# Micro.net
KiCad netlist of a schematic drawn in Altium Designer
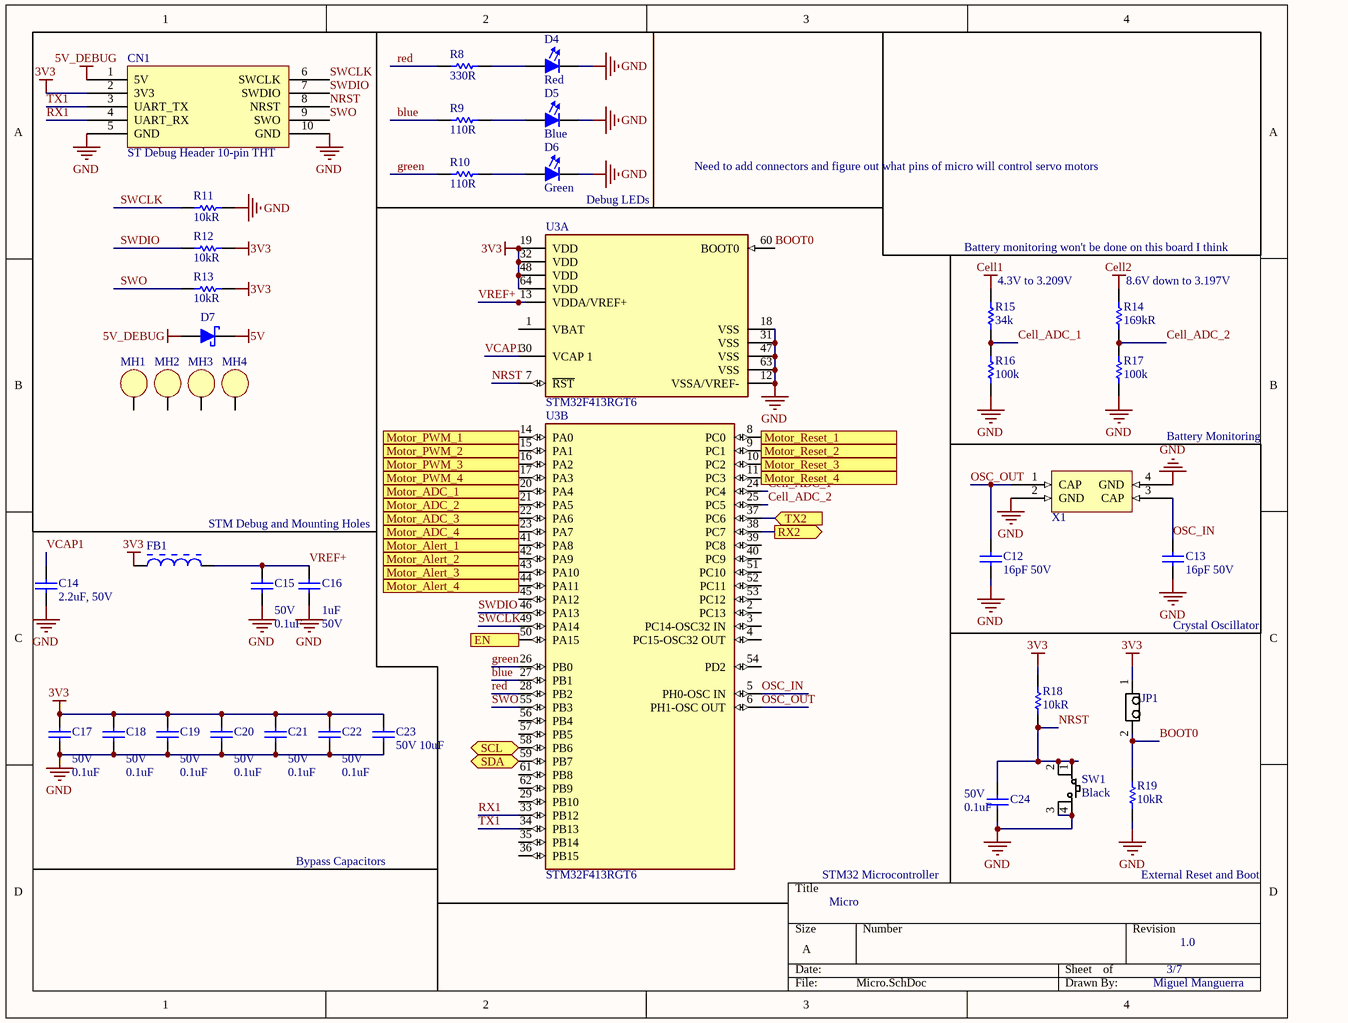
[diagram p0: Micro.SchDoc]

(export (version "E")
  (design (tool "Eeschema 10.0.6"))
  (components
    (comp (ref "C12")
      (value "16pF Ceramic 50V 5% 0603")
      (footprint "CAPC1608X90X35ML10T15")
      (description "Cap Ceramic 16pF 50V C0G 5% SMD 0603 125C Paper T/R")
      (fields (field (name "VOLTAGE") "16pF 50V") (field (name "TOLERANCE") "5%"))
      (libsource (lib "AUVIC") (part "CAP"))
    )
    (comp (ref "C13")
      (value "16pF Ceramic 50V 5% 0603")
      (footprint "CAPC1608X90X35ML10T15")
      (description "Cap Ceramic 16pF 50V C0G 5% SMD 0603 125C Paper T/R")
      (fields (field (name "VOLTAGE") "16pF 50V") (field (name "TOLERANCE") "5%"))
      (libsource (lib "AUVIC") (part "CAP"))
    )
    (comp (ref "C14")
      (value "2.2uF, 50V")
      (footprint "CAPC1608N(0603\")")
      (description "Capacitor, Ceramic, 50V, 10%, 0603 SMD, X5R")
      (fields (field (name "MADE BY") "*") (field (name "PUBLISHER") "AUVic"))
      (libsource (lib "") (part "Symbol_5"))
    )
    (comp (ref "C15")
      (value "CL10B104JB8NNNC")
      (footprint "FP-CL10-0_1-MFG")
      (description "CAP CER 0.1UF 50V X7R 0603")
      (fields
        (field (name "TOLERANCE") "5%")
        (field (name "VOLTAGE") "50V")
        (field (name "CAPACITANCE") "0.1uF")
      )
      (libsource (lib "AUVIC") (part "CAP-NP-2"))
    )
    (comp (ref "C16")
      (value "CL21B105KBFNNNG")
      (footprint "0803 CAP")
      (description "SAMSUNG ELECTRO-MECHANICS - CL21B105KBFNNNG - MLCC CAPACITORS")
      (fields
        (field (name "TOLERANCE") "10%")
        (field (name "CAPACITANCE") "1uF")
        (field (name "VOLTAGE") "50V")
      )
      (libsource (lib "") (part "Symbol_4"))
    )
    (comp (ref "C17")
      (value "CL10B104JB8NNNC")
      (footprint "FP-CL10-0_1-MFG")
      (description "CAP CER 0.1UF 50V X7R 0603")
      (fields
        (field (name "TOLERANCE") "5%")
        (field (name "VOLTAGE") "50V")
        (field (name "CAPACITANCE") "0.1uF")
      )
      (libsource (lib "AUVIC") (part "CAP-NP-2"))
    )
    (comp (ref "C18")
      (value "CL10B104JB8NNNC")
      (footprint "FP-CL10-0_1-MFG")
      (description "CAP CER 0.1UF 50V X7R 0603")
      (fields
        (field (name "TOLERANCE") "5%")
        (field (name "VOLTAGE") "50V")
        (field (name "CAPACITANCE") "0.1uF")
      )
      (libsource (lib "AUVIC") (part "CAP-NP-2"))
    )
    (comp (ref "C19")
      (value "CL10B104JB8NNNC")
      (footprint "FP-CL10-0_1-MFG")
      (description "CAP CER 0.1UF 50V X7R 0603")
      (fields
        (field (name "TOLERANCE") "5%")
        (field (name "VOLTAGE") "50V")
        (field (name "CAPACITANCE") "0.1uF")
      )
      (libsource (lib "AUVIC") (part "CAP-NP-2"))
    )
    (comp (ref "C20")
      (value "CL10B104JB8NNNC")
      (footprint "FP-CL10-0_1-MFG")
      (description "CAP CER 0.1UF 50V X7R 0603")
      (fields
        (field (name "TOLERANCE") "5%")
        (field (name "VOLTAGE") "50V")
        (field (name "CAPACITANCE") "0.1uF")
      )
      (libsource (lib "AUVIC") (part "CAP-NP-2"))
    )
    (comp (ref "C21")
      (value "CL10B104JB8NNNC")
      (footprint "FP-CL10-0_1-MFG")
      (description "CAP CER 0.1UF 50V X7R 0603")
      (fields
        (field (name "TOLERANCE") "5%")
        (field (name "VOLTAGE") "50V")
        (field (name "CAPACITANCE") "0.1uF")
      )
      (libsource (lib "AUVIC") (part "CAP-NP-2"))
    )
    (comp (ref "C22")
      (value "CL10B104JB8NNNC")
      (footprint "FP-CL10-0_1-MFG")
      (description "CAP CER 0.1UF 50V X7R 0603")
      (fields
        (field (name "TOLERANCE") "5%")
        (field (name "VOLTAGE") "50V")
        (field (name "CAPACITANCE") "0.1uF")
      )
      (libsource (lib "AUVIC") (part "CAP-NP-2"))
    )
    (comp (ref "C23")
      (value "50V 10uF")
      (footprint "CAPC3216X180X50LL20T30")
      (description "Cap Ceramic 10uF 50V X7R 10% Pad SMD 1206 125°C T/R")
      (fields (field (name "TOLERANCE") "10%"))
      (libsource (lib "AUVIC") (part "CAP-NP-2"))
    )
    (comp (ref "C24")
      (value "CL10B104JB8NNNC")
      (footprint "FP-CL10-0_1-MFG")
      (description "CAP CER 0.1UF 50V X7R 0603")
      (fields
        (field (name "TOLERANCE") "5%")
        (field (name "VOLTAGE") "50V")
        (field (name "CAPACITANCE") "0.1uF")
      )
      (libsource (lib "AUVIC") (part "CAP-NP-2"))
    )
    (comp (ref "CN1")
      (value "ST Debug Header 10-pin THT")
      (footprint "10-pin shrouded header THT")
      (description "CONN HEADER VERT 10POS 2.54MM")
      (libsource (lib "AUVIC") (part "ST Debug Header 10-pin"))
    )
    (comp (ref "D4")
      (value "Red")
      (footprint "FP-LB_Q39E-MFG")
      (description "LED Red 645nm 2-Pin Chip 0603(1608Metric) T/R")
      (libsource (lib "") (part "Symbol_2"))
    )
    (comp (ref "D5")
      (value "Blue")
      (footprint "FP-LB_Q39E-MFG")
      (description "LED BLUE DIFFUSED 0603 SMD")
      (libsource (lib "") (part "Symbol_2"))
    )
    (comp (ref "D6")
      (value "Green")
      (footprint "FP-LB_Q39E-MFG")
      (description "LED GREEN DIFFUSED 0603 SMD")
      (libsource (lib "") (part "Symbol_2"))
    )
    (comp (ref "D7")
      (value "CUS08F30,H3F")
      (footprint "SC-76")
      (description "Diode Schottky 30V 800mA Surface Mount USC")
      (libsource (lib "AUVIC") (part "Symbol"))
    )
    (comp (ref "FB1")
      (value "BLM18AG601SN1D")
      (footprint "MURA-BLM18-F-H1-CHIP-2_V")
      (fields (field (name "TOLERANCE") "25%"))
      (libsource (lib "AUVIC") (part "MURA-FB-2"))
    )
    (comp (ref "JP1")
      (value "1x2 Male Header")
      (footprint "2X1 Males Header")
      (fields (field (name "MADE BY") "Andy Bates"))
      (libsource (lib "AUVIC") (part "1x2 Male Header"))
    )
    (comp (ref "MH1")
      (value "Mount_Hole_3mm")
      (footprint "Mount-Hole_3mm")
      (description "Mounting hold for M3 hex standoff")
      (libsource (lib "AUVIC") (part "Mount_Hole_3mm"))
    )
    (comp (ref "MH2")
      (value "Mount_Hole_3mm")
      (footprint "Mount-Hole_3mm")
      (description "Mounting hold for M3 hex standoff")
      (libsource (lib "AUVIC") (part "Mount_Hole_3mm"))
    )
    (comp (ref "MH3")
      (value "Mount_Hole_3mm")
      (footprint "Mount-Hole_3mm")
      (description "Mounting hold for M3 hex standoff")
      (libsource (lib "AUVIC") (part "Mount_Hole_3mm"))
    )
    (comp (ref "MH4")
      (value "Mount_Hole_3mm")
      (footprint "Mount-Hole_3mm")
      (description "Mounting hold for M3 hex standoff")
      (libsource (lib "AUVIC") (part "Mount_Hole_3mm"))
    )
    (comp (ref "R8")
      (value "CRCW0603330RFKEA")
      (footprint "FP-CRCW0603-e3-IPC_C")
      (description "Res Thick Film 0603 330 Ohm 1% 0.1W(1/10W) +/-100ppm/ßC Pad SMD Automotive T/R")
      (fields (field (name "TOLERANCE") "1%") (field (name "RESISTANCE") "330R"))
      (libsource (lib "AUVIC") (part "RES"))
    )
    (comp (ref "R9")
      (value "RC0603FR-07110RL")
      (footprint "RESC1608X55X25ML10T15")
      (description "RES SMD 110 OHM 1% 1/10W 0603")
      (fields (field (name "TOLERANCE") "1%") (field (name "RESISTANCE") "110R"))
      (libsource (lib "AUVIC") (part "RES"))
    )
    (comp (ref "R10")
      (value "RC0603FR-07110RL")
      (footprint "RESC1608X55X25ML10T15")
      (description "RES SMD 110 OHM 1% 1/10W 0603")
      (fields (field (name "TOLERANCE") "1%") (field (name "RESISTANCE") "110R"))
      (libsource (lib "AUVIC") (part "RES"))
    )
    (comp (ref "R11")
      (value "10kR")
      (footprint "RESC1608N(0603\")")
      (description "10kR, 1%, 1/10W, 0603 SMD")
      (fields (field (name "MADE BY") "Ashwin Sira"))
      (libsource (lib "") (part "Symbol_1"))
    )
    (comp (ref "R12")
      (value "10kR")
      (footprint "RESC1608N(0603\")")
      (description "10kR, 1%, 1/10W, 0603 SMD")
      (fields (field (name "MADE BY") "Ashwin Sira"))
      (libsource (lib "") (part "Symbol_1"))
    )
    (comp (ref "R13")
      (value "10kR")
      (footprint "RESC1608N(0603\")")
      (description "10kR, 1%, 1/10W, 0603 SMD")
      (fields (field (name "MADE BY") "Ashwin Sira"))
      (libsource (lib "") (part "Symbol_1"))
    )
    (comp (ref "R14")
      (value "169kR, 1%, 1/10W, 0603")
      (footprint "RESC0603(1608)_M")
      (description "RES 169K OHM 1% 1/10W 0603")
      (fields (field (name "RESISTANCE") "169kR") (field (name "TOLERANCE") "1%"))
      (libsource (lib "AUVIC") (part "RES"))
    )
    (comp (ref "R15")
      (value "34kR, 1%, 1/10W, 0603")
      (footprint "RESC1608N(0603\")")
      (description "RES 34K OHM 1/10W 1% 0603 SMD")
      (fields
        (field (name "RESISTANCE") "34k")
        (field (name "MANUFACTURER PART NUMBER") "RC0603FR-0734KL")
        (field (name "MANUFACTURER") "Yageo")
      )
      (libsource (lib "AUVIC") (part "34kR, 1%, 1/10W, 0603"))
    )
    (comp (ref "R16")
      (value "100k")
      (footprint "RESC1608N(0603\")")
      (description "100kR, 1%, 1/10W, 0603 SMD")
      (fields (field (name "MADE BY") "Andy Bates"))
      (libsource (lib "") (part "Symbol_1"))
    )
    (comp (ref "R17")
      (value "100k")
      (footprint "RESC1608N(0603\")")
      (description "100kR, 1%, 1/10W, 0603 SMD")
      (fields (field (name "MADE BY") "Andy Bates"))
      (libsource (lib "") (part "Symbol_1"))
    )
    (comp (ref "R18")
      (value "10kR")
      (footprint "RESC1608N(0603\")")
      (description "10kR, 1%, 1/10W, 0603 SMD")
      (fields (field (name "MADE BY") "Ashwin Sira"))
      (libsource (lib "") (part "Symbol_1"))
    )
    (comp (ref "R19")
      (value "10kR")
      (footprint "RESC1608N(0603\")")
      (description "10kR, 1%, 1/10W, 0603 SMD")
      (fields (field (name "MADE BY") "Ashwin Sira"))
      (libsource (lib "") (part "Symbol_1"))
    )
    (comp (ref "SW1")
      (value "PTS645SL43SMTR92LFS")
      (footprint "4-SPST-NO")
      (description "Black Switch Tactile N.O. SPST Round Button Gull Wing 0.05A 12VDC 100000Cycles 1.27N SMD T/R")
      (fields (field (name "BUTTON COLOUR") "Black"))
      (libsource (lib "") (part "Symbol_3"))
    )
    (comp (ref "U3")
      (value "STM32F413RGT6")
      (footprint "FP-LQFP64-5W-MFG")
      (description "STMICROELECTRONICS - STM32F413RGT6 - MCU, ARM CORTEX-M4, 100MHZ, LQFP-64")
      (libsource (lib "AUVIC") (part "7f3deadac312a1e532344b4e443717e"))
    )
    (comp (ref "X1")
      (value "CRYSTAL 8.0MHZ 16PF SMD")
      (footprint "QFN250P750X520X140_HS-5M")
      (description "8MHz ±30ppm Crystal 16pF 80 Ohms 4-SMD, No Lead")
      (libsource (lib "AUVIC") (part "LFXTAL026380REEL"))
    )
  )
  (nets
    (net (code "1") (name "/BOOT0") (class "Default")
      (node (ref "JP1") (pin "2") (pinfunction "2_2") (pintype "passive"))
      (node (ref "R19") (pin "1") (pinfunction "1_1") (pintype "passive"))
      (node (ref "U3") (pin "60") (pinfunction "BOOT0_60") (pintype "input"))
    )
    (net (code "2") (name "/Cell_ADC_1") (class "Default")
      (node (ref "R15") (pin "1") (pinfunction "1_1") (pintype "passive"))
      (node (ref "R16") (pin "2") (pinfunction "2_2") (pintype "passive"))
      (node (ref "U3") (pin "24") (pinfunction "PC4_24") (pintype "bidirectional"))
    )
    (net (code "3") (name "/Cell_ADC_2") (class "Default")
      (node (ref "R14") (pin "1") (pinfunction "1_1") (pintype "passive"))
      (node (ref "R17") (pin "2") (pinfunction "2_2") (pintype "passive"))
      (node (ref "U3") (pin "25") (pinfunction "PC5_25") (pintype "bidirectional"))
    )
    (net (code "4") (name "/EN") (class "Default")
      (node (ref "U3") (pin "50") (pinfunction "PA15_50") (pintype "bidirectional"))
    )
    (net (code "5") (name "/Motor_ADC_1") (class "Default")
      (node (ref "U3") (pin "20") (pinfunction "PA4_20") (pintype "bidirectional"))
    )
    (net (code "6") (name "/Motor_ADC_2") (class "Default")
      (node (ref "U3") (pin "21") (pinfunction "PA5_21") (pintype "bidirectional"))
    )
    (net (code "7") (name "/Motor_ADC_3") (class "Default")
      (node (ref "U3") (pin "22") (pinfunction "PA6_22") (pintype "bidirectional"))
    )
    (net (code "8") (name "/Motor_ADC_4") (class "Default")
      (node (ref "U3") (pin "23") (pinfunction "PA7_23") (pintype "bidirectional"))
    )
    (net (code "9") (name "/Motor_Alert_1") (class "Default")
      (node (ref "U3") (pin "41") (pinfunction "PA8_41") (pintype "bidirectional"))
    )
    (net (code "10") (name "/Motor_Alert_2") (class "Default")
      (node (ref "U3") (pin "42") (pinfunction "PA9_42") (pintype "bidirectional"))
    )
    (net (code "11") (name "/Motor_Alert_3") (class "Default")
      (node (ref "U3") (pin "43") (pinfunction "PA10_43") (pintype "bidirectional"))
    )
    (net (code "12") (name "/Motor_Alert_4") (class "Default")
      (node (ref "U3") (pin "44") (pinfunction "PA11_44") (pintype "bidirectional"))
    )
    (net (code "13") (name "/Motor_PWM_1") (class "Default")
      (node (ref "U3") (pin "14") (pinfunction "PA0_14") (pintype "bidirectional"))
    )
    (net (code "14") (name "/Motor_PWM_2") (class "Default")
      (node (ref "U3") (pin "15") (pinfunction "PA1_15") (pintype "bidirectional"))
    )
    (net (code "15") (name "/Motor_PWM_3") (class "Default")
      (node (ref "U3") (pin "16") (pinfunction "PA2_16") (pintype "bidirectional"))
    )
    (net (code "16") (name "/Motor_PWM_4") (class "Default")
      (node (ref "U3") (pin "17") (pinfunction "PA3_17") (pintype "bidirectional"))
    )
    (net (code "17") (name "/Motor_Reset_1") (class "Default")
      (node (ref "U3") (pin "8") (pinfunction "PC0_8") (pintype "bidirectional"))
    )
    (net (code "18") (name "/Motor_Reset_2") (class "Default")
      (node (ref "U3") (pin "9") (pinfunction "PC1_9") (pintype "bidirectional"))
    )
    (net (code "19") (name "/Motor_Reset_3") (class "Default")
      (node (ref "U3") (pin "10") (pinfunction "PC2_10") (pintype "bidirectional"))
    )
    (net (code "20") (name "/Motor_Reset_4") (class "Default")
      (node (ref "U3") (pin "11") (pinfunction "PC3_11") (pintype "bidirectional"))
    )
    (net (code "21") (name "/NRST") (class "Default")
      (node (ref "C24") (pin "1") (pinfunction "1_1") (pintype "passive"))
      (node (ref "CN1") (pin "8") (pinfunction "NRST_8") (pintype "passive"))
      (node (ref "R18") (pin "2") (pinfunction "2_2") (pintype "passive"))
      (node (ref "SW1") (pin "1") (pinfunction "1_1") (pintype "passive"))
      (node (ref "SW1") (pin "2") (pinfunction "2_2") (pintype "passive"))
      (node (ref "U3") (pin "7") (pinfunction "~{RST}_7") (pintype "bidirectional"))
    )
    (net (code "22") (name "/OSC_IN") (class "Default")
      (node (ref "C13") (pin "2") (pinfunction "2_2") (pintype "passive"))
      (node (ref "U3") (pin "5") (pinfunction "PH0-OSC_IN_5") (pintype "bidirectional"))
      (node (ref "X1") (pin "3") (pinfunction "CAP_3") (pintype "input"))
    )
    (net (code "23") (name "/OSC_OUT") (class "Default")
      (node (ref "C12") (pin "2") (pinfunction "2_2") (pintype "passive"))
      (node (ref "U3") (pin "6") (pinfunction "PH1-OSC_OUT_6") (pintype "bidirectional"))
      (node (ref "X1") (pin "1") (pinfunction "CAP_1") (pintype "input"))
    )
    (net (code "24") (name "/RX1") (class "Default")
      (node (ref "CN1") (pin "4") (pinfunction "UART_RX_4") (pintype "passive"))
      (node (ref "U3") (pin "33") (pinfunction "PB12_33") (pintype "bidirectional"))
    )
    (net (code "25") (name "/RX2") (class "Default")
      (node (ref "U3") (pin "38") (pinfunction "PC7_38") (pintype "bidirectional"))
    )
    (net (code "26") (name "/SCL") (class "Default")
      (node (ref "U3") (pin "58") (pinfunction "PB6_58") (pintype "bidirectional"))
    )
    (net (code "27") (name "/SDA") (class "Default")
      (node (ref "U3") (pin "59") (pinfunction "PB7_59") (pintype "bidirectional"))
    )
    (net (code "28") (name "/SWCLK") (class "Default")
      (node (ref "CN1") (pin "6") (pinfunction "SWCLK_6") (pintype "passive"))
      (node (ref "R11") (pin "2") (pinfunction "2_2") (pintype "passive"))
      (node (ref "U3") (pin "49") (pinfunction "PA14_49") (pintype "bidirectional"))
    )
    (net (code "29") (name "/SWDIO") (class "Default")
      (node (ref "CN1") (pin "7") (pinfunction "SWDIO_7") (pintype "passive"))
      (node (ref "R12") (pin "2") (pinfunction "2_2") (pintype "passive"))
      (node (ref "U3") (pin "46") (pinfunction "PA13_46") (pintype "bidirectional"))
    )
    (net (code "30") (name "/SWO") (class "Default")
      (node (ref "CN1") (pin "9") (pinfunction "SWO_9") (pintype "passive"))
      (node (ref "R13") (pin "2") (pinfunction "2_2") (pintype "passive"))
      (node (ref "U3") (pin "55") (pinfunction "PB3_55") (pintype "bidirectional"))
    )
    (net (code "31") (name "/TX1") (class "Default")
      (node (ref "CN1") (pin "3") (pinfunction "UART_TX_3") (pintype "passive"))
      (node (ref "U3") (pin "34") (pinfunction "PB13_34") (pintype "bidirectional"))
    )
    (net (code "32") (name "/TX2") (class "Default")
      (node (ref "U3") (pin "37") (pinfunction "PC6_37") (pintype "bidirectional"))
    )
    (net (code "33") (name "/VCAP1") (class "Default")
      (node (ref "C14") (pin "1") (pinfunction "Anode_1") (pintype "passive"))
      (node (ref "U3") (pin "30") (pinfunction "VCAP_1_30") (pintype "power_in"))
    )
    (net (code "34") (name "/VREF+") (class "Default")
      (node (ref "C15") (pin "1") (pinfunction "1_1") (pintype "passive"))
      (node (ref "C16") (pin "1") (pinfunction "1_1") (pintype "passive"))
      (node (ref "FB1") (pin "2") (pinfunction "2_2") (pintype "passive"))
      (node (ref "U3") (pin "13") (pinfunction "VDDA/VREF+_13") (pintype "power_in"))
    )
    (net (code "35") (name "/blue") (class "Default")
      (node (ref "R9") (pin "1") (pinfunction "1_1") (pintype "passive"))
      (node (ref "U3") (pin "27") (pinfunction "PB1_27") (pintype "bidirectional"))
    )
    (net (code "36") (name "/green") (class "Default")
      (node (ref "R10") (pin "1") (pinfunction "1_1") (pintype "passive"))
      (node (ref "U3") (pin "26") (pinfunction "PB0_26") (pintype "bidirectional"))
    )
    (net (code "37") (name "/red") (class "Default")
      (node (ref "R8") (pin "1") (pinfunction "1_1") (pintype "passive"))
      (node (ref "U3") (pin "28") (pinfunction "PB2_28") (pintype "bidirectional"))
    )
    (net (code "38") (name "3V3") (class "Default")
      (node (ref "C17") (pin "1") (pinfunction "1_1") (pintype "passive"))
      (node (ref "C18") (pin "1") (pinfunction "1_1") (pintype "passive"))
      (node (ref "C19") (pin "1") (pinfunction "1_1") (pintype "passive"))
      (node (ref "C20") (pin "1") (pinfunction "1_1") (pintype "passive"))
      (node (ref "C21") (pin "1") (pinfunction "1_1") (pintype "passive"))
      (node (ref "C22") (pin "1") (pinfunction "1_1") (pintype "passive"))
      (node (ref "C23") (pin "1") (pinfunction "1_1") (pintype "passive"))
      (node (ref "CN1") (pin "2") (pinfunction "3V3_2") (pintype "passive"))
      (node (ref "FB1") (pin "1") (pinfunction "1_1") (pintype "passive"))
      (node (ref "JP1") (pin "1") (pinfunction "1_1") (pintype "passive"))
      (node (ref "R12") (pin "1") (pinfunction "1_1") (pintype "passive"))
      (node (ref "R13") (pin "1") (pinfunction "1_1") (pintype "passive"))
      (node (ref "R18") (pin "1") (pinfunction "1_1") (pintype "passive"))
      (node (ref "U3") (pin "19") (pinfunction "VDD_19") (pintype "power_in"))
      (node (ref "U3") (pin "32") (pinfunction "VDD_32") (pintype "power_in"))
      (node (ref "U3") (pin "48") (pinfunction "VDD_48") (pintype "power_in"))
      (node (ref "U3") (pin "64") (pinfunction "VDD_64") (pintype "power_in"))
    )
    (net (code "39") (name "5V") (class "Default")
      (node (ref "D7") (pin "K") (pinfunction "Cathode_K") (pintype "passive"))
    )
    (net (code "40") (name "5V_DEBUG") (class "Default")
      (node (ref "CN1") (pin "1") (pinfunction "5V_1") (pintype "passive"))
      (node (ref "D7") (pin "A") (pinfunction "Anode_A") (pintype "passive"))
    )
    (net (code "41") (name "Cell1") (class "Default")
      (node (ref "R15") (pin "2") (pinfunction "2_2") (pintype "passive"))
    )
    (net (code "42") (name "Cell2") (class "Default")
      (node (ref "R14") (pin "2") (pinfunction "2_2") (pintype "passive"))
    )
    (net (code "43") (name "GND") (class "Default")
      (node (ref "C12") (pin "1") (pinfunction "1_1") (pintype "passive"))
      (node (ref "C13") (pin "1") (pinfunction "1_1") (pintype "passive"))
      (node (ref "C14") (pin "2") (pinfunction "Cathode_2") (pintype "passive"))
      (node (ref "C15") (pin "2") (pinfunction "2_2") (pintype "passive"))
      (node (ref "C16") (pin "2") (pinfunction "2_2") (pintype "passive"))
      (node (ref "C17") (pin "2") (pinfunction "2_2") (pintype "passive"))
      (node (ref "C18") (pin "2") (pinfunction "2_2") (pintype "passive"))
      (node (ref "C19") (pin "2") (pinfunction "2_2") (pintype "passive"))
      (node (ref "C20") (pin "2") (pinfunction "2_2") (pintype "passive"))
      (node (ref "C21") (pin "2") (pinfunction "2_2") (pintype "passive"))
      (node (ref "C22") (pin "2") (pinfunction "2_2") (pintype "passive"))
      (node (ref "C23") (pin "2") (pinfunction "2_2") (pintype "passive"))
      (node (ref "C24") (pin "2") (pinfunction "2_2") (pintype "passive"))
      (node (ref "CN1") (pin "10") (pinfunction "GND_10") (pintype "passive"))
      (node (ref "CN1") (pin "5") (pinfunction "GND_5") (pintype "passive"))
      (node (ref "D4") (pin "1") (pinfunction "Cathode_1") (pintype "passive"))
      (node (ref "D5") (pin "1") (pinfunction "Cathode_1") (pintype "passive"))
      (node (ref "D6") (pin "1") (pinfunction "Cathode_1") (pintype "passive"))
      (node (ref "R11") (pin "1") (pinfunction "1_1") (pintype "passive"))
      (node (ref "R16") (pin "1") (pinfunction "1_1") (pintype "passive"))
      (node (ref "R17") (pin "1") (pinfunction "1_1") (pintype "passive"))
      (node (ref "R19") (pin "2") (pinfunction "2_2") (pintype "passive"))
      (node (ref "SW1") (pin "3") (pinfunction "3_3") (pintype "passive"))
      (node (ref "SW1") (pin "4") (pinfunction "4_4") (pintype "passive"))
      (node (ref "U3") (pin "12") (pinfunction "VSSA/VREF-_12") (pintype "power_in"))
      (node (ref "U3") (pin "18") (pinfunction "VSS_18") (pintype "power_in"))
      (node (ref "U3") (pin "31") (pinfunction "VSS_31") (pintype "power_in"))
      (node (ref "U3") (pin "47") (pinfunction "VSS_47") (pintype "power_in"))
      (node (ref "U3") (pin "63") (pinfunction "VSS_63") (pintype "power_in"))
      (node (ref "X1") (pin "2") (pinfunction "GND_2") (pintype "input"))
      (node (ref "X1") (pin "4") (pinfunction "GND_4") (pintype "input"))
    )
    (net (code "44") (name "Net-(D4-Anode)") (class "Default")
      (node (ref "D4") (pin "2") (pinfunction "Anode_2") (pintype "passive"))
      (node (ref "R8") (pin "2") (pinfunction "2_2") (pintype "passive"))
    )
    (net (code "45") (name "Net-(D5-Anode)") (class "Default")
      (node (ref "D5") (pin "2") (pinfunction "Anode_2") (pintype "passive"))
      (node (ref "R9") (pin "2") (pinfunction "2_2") (pintype "passive"))
    )
    (net (code "46") (name "Net-(D6-Anode)") (class "Default")
      (node (ref "D6") (pin "2") (pinfunction "Anode_2") (pintype "passive"))
      (node (ref "R10") (pin "2") (pinfunction "2_2") (pintype "passive"))
    )
    (net (code "47") (name "unconnected-(MH1-Pad1)") (class "Default")
      (node (ref "MH1") (pin "1") (pinfunction "1_1") (pintype "passive"))
    )
    (net (code "48") (name "unconnected-(MH2-Pad1)") (class "Default")
      (node (ref "MH2") (pin "1") (pinfunction "1_1") (pintype "passive"))
    )
    (net (code "49") (name "unconnected-(MH3-Pad1)") (class "Default")
      (node (ref "MH3") (pin "1") (pinfunction "1_1") (pintype "passive"))
    )
    (net (code "50") (name "unconnected-(MH4-Pad1)") (class "Default")
      (node (ref "MH4") (pin "1") (pinfunction "1_1") (pintype "passive"))
    )
    (net (code "51") (name "unconnected-(U3A-VBAT-Pad1)") (class "Default")
      (node (ref "U3") (pin "1") (pinfunction "VBAT_1") (pintype "power_in"))
    )
    (net (code "52") (name "unconnected-(U3B-PA12-Pad45)") (class "Default")
      (node (ref "U3") (pin "45") (pinfunction "PA12_45") (pintype "bidirectional"))
    )
    (net (code "53") (name "unconnected-(U3B-PB4-Pad56)") (class "Default")
      (node (ref "U3") (pin "56") (pinfunction "PB4_56") (pintype "bidirectional"))
    )
    (net (code "54") (name "unconnected-(U3B-PB5-Pad57)") (class "Default")
      (node (ref "U3") (pin "57") (pinfunction "PB5_57") (pintype "bidirectional"))
    )
    (net (code "55") (name "unconnected-(U3B-PB8-Pad61)") (class "Default")
      (node (ref "U3") (pin "61") (pinfunction "PB8_61") (pintype "bidirectional"))
    )
    (net (code "56") (name "unconnected-(U3B-PB9-Pad62)") (class "Default")
      (node (ref "U3") (pin "62") (pinfunction "PB9_62") (pintype "bidirectional"))
    )
    (net (code "57") (name "unconnected-(U3B-PB10-Pad29)") (class "Default")
      (node (ref "U3") (pin "29") (pinfunction "PB10_29") (pintype "bidirectional"))
    )
    (net (code "58") (name "unconnected-(U3B-PB14-Pad35)") (class "Default")
      (node (ref "U3") (pin "35") (pinfunction "PB14_35") (pintype "bidirectional"))
    )
    (net (code "59") (name "unconnected-(U3B-PB15-Pad36)") (class "Default")
      (node (ref "U3") (pin "36") (pinfunction "PB15_36") (pintype "bidirectional"))
    )
    (net (code "60") (name "unconnected-(U3B-PC8-Pad39)") (class "Default")
      (node (ref "U3") (pin "39") (pinfunction "PC8_39") (pintype "bidirectional"))
    )
    (net (code "61") (name "unconnected-(U3B-PC9-Pad40)") (class "Default")
      (node (ref "U3") (pin "40") (pinfunction "PC9_40") (pintype "bidirectional"))
    )
    (net (code "62") (name "unconnected-(U3B-PC10-Pad51)") (class "Default")
      (node (ref "U3") (pin "51") (pinfunction "PC10_51") (pintype "bidirectional"))
    )
    (net (code "63") (name "unconnected-(U3B-PC11-Pad52)") (class "Default")
      (node (ref "U3") (pin "52") (pinfunction "PC11_52") (pintype "bidirectional"))
    )
    (net (code "64") (name "unconnected-(U3B-PC12-Pad53)") (class "Default")
      (node (ref "U3") (pin "53") (pinfunction "PC12_53") (pintype "bidirectional"))
    )
    (net (code "65") (name "unconnected-(U3B-PC13-Pad2)") (class "Default")
      (node (ref "U3") (pin "2") (pinfunction "PC13_2") (pintype "bidirectional"))
    )
    (net (code "66") (name "unconnected-(U3B-PC14-OSC32_IN-Pad3)") (class "Default")
      (node (ref "U3") (pin "3") (pinfunction "PC14-OSC32_IN_3") (pintype "bidirectional"))
    )
    (net (code "67") (name "unconnected-(U3B-PC15-OSC32_OUT-Pad4)") (class "Default")
      (node (ref "U3") (pin "4") (pinfunction "PC15-OSC32_OUT_4") (pintype "bidirectional"))
    )
    (net (code "68") (name "unconnected-(U3B-PD2-Pad54)") (class "Default")
      (node (ref "U3") (pin "54") (pinfunction "PD2_54") (pintype "bidirectional"))
    )
  )
)
